# 03_-_WiFi.net
KiCad netlist of a schematic drawn in Altium Designer
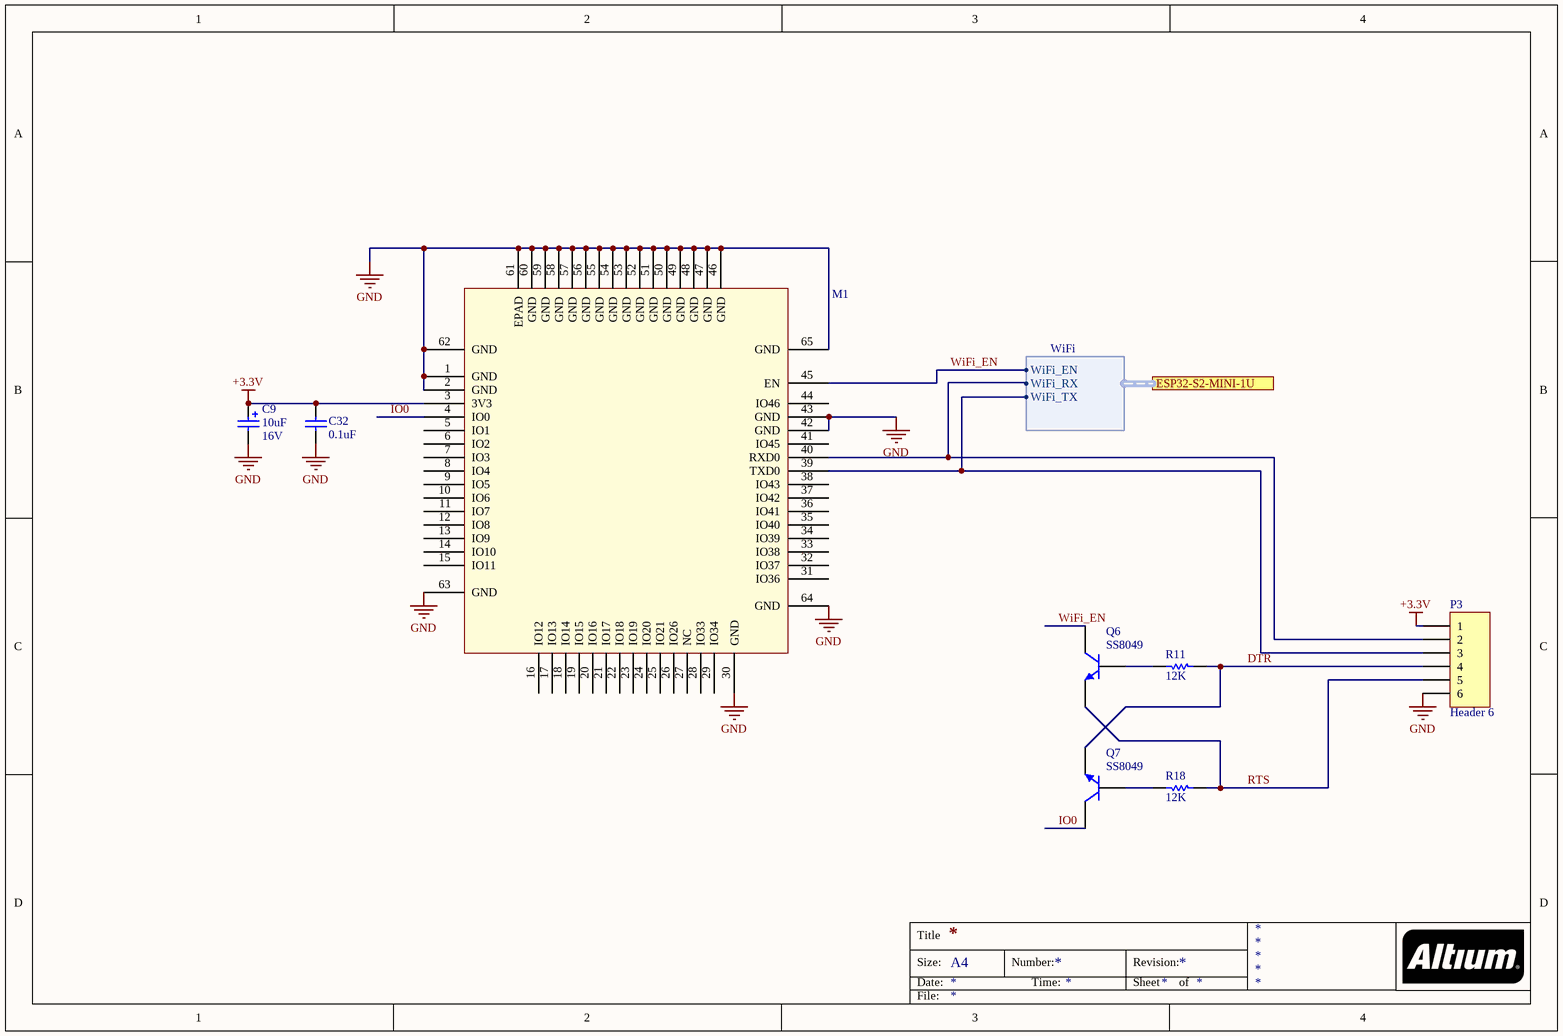
[diagram p0: [03] - WiFi.SchDoc]

(export (version "E")
  (design (tool "Eeschema 10.0.6"))
  (components
    (comp (ref "C9")
      (value "Capacitor Polarized")
      (footprint "Tantalum 3216 A")
      (description "CAP TANT 10UF 10% 16V 1206")
      (fields
        (field (name "MANUFACTURER") "Vishay Sprague")
        (field (name "MANUFACTURER PART NUMBER") "293D106X9016A2TE3")
        (field (name "CAPACITANCE") "10uF")
        (field (name "VOLTAGE RATING") "16V")
      )
      (libsource (lib "Altium_Library") (part "Capacitor Polarized"))
    )
    (comp (ref "C32")
      (value "0.1uF")
      (footprint "0603_C")
      (description "Capacitor")
      (fields (field (name "Comment") "Cap"))
      (libsource (lib "MyLib") (part "Cap"))
    )
    (comp (ref "M1")
      (value "ESP32-S2-MINI-1U _Module")
      (footprint "ESP32-S2-MINI-1U")
      (description "Wi-Fi module")
      (libsource (lib "Blue Tractor-2021") (part "ESP32-S2-MINI-1U _Module"))
    )
    (comp (ref "P3")
      (value "Header 6")
      (footprint "HDR1X6")
      (description "Header, 6-Pin")
      (fields (field (name "PUBLISHER") "Altium Limited"))
      (libsource (lib "Miscellaneous Connectors") (part "Header 6"))
    )
    (comp (ref "Q6")
      (value "SS8049")
      (footprint "SOT23-3")
      (description "NPN Bipolar Transistor")
      (fields (field (name "PUBLISHER") "Altium Limited"))
      (libsource (lib "Miscellaneous Devices") (part "NPN"))
    )
    (comp (ref "Q7")
      (value "SS8049")
      (footprint "SOT23-3")
      (description "NPN Bipolar Transistor")
      (fields (field (name "PUBLISHER") "Altium Limited"))
      (libsource (lib "Miscellaneous Devices") (part "NPN"))
    )
    (comp (ref "R11")
      (value "Res1")
      (footprint "Res-0603")
      (description "Res Thkflm Anti-sulfurated 0603 100K Ohm 5% SMD")
      (fields
        (field (name "MANUFACTURER") "Panasonic")
        (field (name "MANUFACTURER PART NUMBER") "ERJ-U03J104V")
        (field (name "RESISTANCE") "12K")
      )
      (libsource (lib "Altium_Library") (part "Res1"))
    )
    (comp (ref "R18")
      (value "Res1")
      (footprint "Res-0603")
      (description "Res Thkflm Anti-sulfurated 0603 100K Ohm 5% SMD")
      (fields
        (field (name "MANUFACTURER") "Panasonic")
        (field (name "MANUFACTURER PART NUMBER") "ERJ-U03J104V")
        (field (name "RESISTANCE") "12K")
      )
      (libsource (lib "Altium_Library") (part "Res1"))
    )
  )
  (nets
    (net (code "2") (name "+3.3V") (class "Default")
      (node (ref "C32") (pin "2") (pinfunction "2_2") (pintype "passive"))
      (node (ref "C9") (pin "1") (pinfunction "1_1") (pintype "passive"))
      (node (ref "M1") (pin "3") (pinfunction "3V3_3") (pintype "power_in"))
      (node (ref "P3") (pin "1") (pinfunction "1_1") (pintype "passive"))
    )
    (net (code "3") (name "/DTR") (class "Default")
      (node (ref "P3") (pin "4") (pinfunction "4_4") (pintype "passive"))
      (node (ref "Q7") (pin "2") (pinfunction "E_2") (pintype "passive"))
      (node (ref "R11") (pin "2") (pinfunction "2_2") (pintype "passive"))
    )
    (net (code "4") (name "/IO0") (class "Default")
      (node (ref "M1") (pin "4") (pinfunction "IO0_4") (pintype "passive"))
      (node (ref "Q7") (pin "3") (pinfunction "C_3") (pintype "passive"))
    )
    (net (code "5") (name "/RTS") (class "Default")
      (node (ref "P3") (pin "5") (pinfunction "5_5") (pintype "passive"))
      (node (ref "Q6") (pin "2") (pinfunction "E_2") (pintype "passive"))
      (node (ref "R18") (pin "2") (pinfunction "2_2") (pintype "passive"))
    )
    (net (code "6") (name "/WiFi_EN") (class "Default")
      (node (ref "M1") (pin "45") (pinfunction "EN_45") (pintype "power_in"))
      (node (ref "Q6") (pin "3") (pinfunction "C_3") (pintype "passive"))
    )
    (net (code "8") (name "GND") (class "Default")
      (node (ref "C32") (pin "1") (pinfunction "1_1") (pintype "passive"))
      (node (ref "C9") (pin "2") (pinfunction "2_2") (pintype "passive"))
      (node (ref "M1") (pin "1") (pinfunction "GND_1") (pintype "power_in"))
      (node (ref "M1") (pin "2") (pinfunction "GND_2") (pintype "power_in"))
      (node (ref "M1") (pin "30") (pinfunction "GND_30") (pintype "power_in"))
      (node (ref "M1") (pin "42") (pinfunction "GND_42") (pintype "passive"))
      (node (ref "M1") (pin "43") (pinfunction "GND_43") (pintype "passive"))
      (node (ref "M1") (pin "46") (pinfunction "GND_46") (pintype "power_in"))
      (node (ref "M1") (pin "47") (pinfunction "GND_47") (pintype "power_in"))
      (node (ref "M1") (pin "48") (pinfunction "GND_48") (pintype "power_in"))
      (node (ref "M1") (pin "49") (pinfunction "GND_49") (pintype "power_in"))
      (node (ref "M1") (pin "50") (pinfunction "GND_50") (pintype "power_in"))
      (node (ref "M1") (pin "51") (pinfunction "GND_51") (pintype "power_in"))
      (node (ref "M1") (pin "52") (pinfunction "GND_52") (pintype "power_in"))
      (node (ref "M1") (pin "53") (pinfunction "GND_53") (pintype "power_in"))
      (node (ref "M1") (pin "54") (pinfunction "GND_54") (pintype "power_in"))
      (node (ref "M1") (pin "55") (pinfunction "GND_55") (pintype "power_in"))
      (node (ref "M1") (pin "56") (pinfunction "GND_56") (pintype "power_in"))
      (node (ref "M1") (pin "57") (pinfunction "GND_57") (pintype "power_in"))
      (node (ref "M1") (pin "58") (pinfunction "GND_58") (pintype "power_in"))
      (node (ref "M1") (pin "59") (pinfunction "GND_59") (pintype "power_in"))
      (node (ref "M1") (pin "60") (pinfunction "GND_60") (pintype "power_in"))
      (node (ref "M1") (pin "61") (pinfunction "EPAD_61") (pintype "power_in"))
      (node (ref "M1") (pin "62") (pinfunction "GND_62") (pintype "power_in"))
      (node (ref "M1") (pin "63") (pinfunction "GND_63") (pintype "passive"))
      (node (ref "M1") (pin "64") (pinfunction "GND_64") (pintype "passive"))
      (node (ref "M1") (pin "65") (pinfunction "GND_65") (pintype "power_in"))
      (node (ref "P3") (pin "6") (pinfunction "6_6") (pintype "passive"))
    )
    (net (code "9") (name "Net-(M1-RXD0)") (class "Default")
      (node (ref "M1") (pin "40") (pinfunction "RXD0_40") (pintype "passive"))
      (node (ref "P3") (pin "2") (pinfunction "2_2") (pintype "passive"))
    )
    (net (code "10") (name "Net-(M1-TXD0)") (class "Default")
      (node (ref "M1") (pin "39") (pinfunction "TXD0_39") (pintype "passive"))
      (node (ref "P3") (pin "3") (pinfunction "3_3") (pintype "passive"))
    )
    (net (code "11") (name "Net-(Q6-B)") (class "Default")
      (node (ref "Q6") (pin "1") (pinfunction "B_1") (pintype "passive"))
      (node (ref "R11") (pin "1") (pinfunction "1_1") (pintype "passive"))
    )
    (net (code "12") (name "Net-(Q7-B)") (class "Default")
      (node (ref "Q7") (pin "1") (pinfunction "B_1") (pintype "passive"))
      (node (ref "R18") (pin "1") (pinfunction "1_1") (pintype "passive"))
    )
    (net (code "13") (name "unconnected-(M1-IO1-Pad5)") (class "Default")
      (node (ref "M1") (pin "5") (pinfunction "IO1_5") (pintype "passive"))
    )
    (net (code "14") (name "unconnected-(M1-IO2-Pad6)") (class "Default")
      (node (ref "M1") (pin "6") (pinfunction "IO2_6") (pintype "passive"))
    )
    (net (code "15") (name "unconnected-(M1-IO3-Pad7)") (class "Default")
      (node (ref "M1") (pin "7") (pinfunction "IO3_7") (pintype "passive"))
    )
    (net (code "16") (name "unconnected-(M1-IO4-Pad8)") (class "Default")
      (node (ref "M1") (pin "8") (pinfunction "IO4_8") (pintype "passive"))
    )
    (net (code "17") (name "unconnected-(M1-IO5-Pad9)") (class "Default")
      (node (ref "M1") (pin "9") (pinfunction "IO5_9") (pintype "passive"))
    )
    (net (code "18") (name "unconnected-(M1-IO6-Pad10)") (class "Default")
      (node (ref "M1") (pin "10") (pinfunction "IO6_10") (pintype "passive"))
    )
    (net (code "19") (name "unconnected-(M1-IO7-Pad11)") (class "Default")
      (node (ref "M1") (pin "11") (pinfunction "IO7_11") (pintype "passive"))
    )
    (net (code "20") (name "unconnected-(M1-IO8-Pad12)") (class "Default")
      (node (ref "M1") (pin "12") (pinfunction "IO8_12") (pintype "passive"))
    )
    (net (code "21") (name "unconnected-(M1-IO9-Pad13)") (class "Default")
      (node (ref "M1") (pin "13") (pinfunction "IO9_13") (pintype "passive"))
    )
    (net (code "22") (name "unconnected-(M1-IO10-Pad14)") (class "Default")
      (node (ref "M1") (pin "14") (pinfunction "IO10_14") (pintype "passive"))
    )
    (net (code "23") (name "unconnected-(M1-IO11-Pad15)") (class "Default")
      (node (ref "M1") (pin "15") (pinfunction "IO11_15") (pintype "passive"))
    )
    (net (code "24") (name "unconnected-(M1-IO12-Pad16)") (class "Default")
      (node (ref "M1") (pin "16") (pinfunction "IO12_16") (pintype "passive"))
    )
    (net (code "25") (name "unconnected-(M1-IO13-Pad17)") (class "Default")
      (node (ref "M1") (pin "17") (pinfunction "IO13_17") (pintype "passive"))
    )
    (net (code "26") (name "unconnected-(M1-IO14-Pad18)") (class "Default")
      (node (ref "M1") (pin "18") (pinfunction "IO14_18") (pintype "passive"))
    )
    (net (code "27") (name "unconnected-(M1-IO15-Pad19)") (class "Default")
      (node (ref "M1") (pin "19") (pinfunction "IO15_19") (pintype "passive"))
    )
    (net (code "28") (name "unconnected-(M1-IO16-Pad20)") (class "Default")
      (node (ref "M1") (pin "20") (pinfunction "IO16_20") (pintype "passive"))
    )
    (net (code "29") (name "unconnected-(M1-IO17-Pad21)") (class "Default")
      (node (ref "M1") (pin "21") (pinfunction "IO17_21") (pintype "passive"))
    )
    (net (code "30") (name "unconnected-(M1-IO18-Pad22)") (class "Default")
      (node (ref "M1") (pin "22") (pinfunction "IO18_22") (pintype "passive"))
    )
    (net (code "31") (name "unconnected-(M1-IO19-Pad23)") (class "Default")
      (node (ref "M1") (pin "23") (pinfunction "IO19_23") (pintype "passive"))
    )
    (net (code "32") (name "unconnected-(M1-IO20-Pad24)") (class "Default")
      (node (ref "M1") (pin "24") (pinfunction "IO20_24") (pintype "passive"))
    )
    (net (code "33") (name "unconnected-(M1-IO21-Pad25)") (class "Default")
      (node (ref "M1") (pin "25") (pinfunction "IO21_25") (pintype "passive"))
    )
    (net (code "34") (name "unconnected-(M1-IO26-Pad26)") (class "Default")
      (node (ref "M1") (pin "26") (pinfunction "IO26_26") (pintype "passive"))
    )
    (net (code "35") (name "unconnected-(M1-IO33-Pad28)") (class "Default")
      (node (ref "M1") (pin "28") (pinfunction "IO33_28") (pintype "passive"))
    )
    (net (code "36") (name "unconnected-(M1-IO34-Pad29)") (class "Default")
      (node (ref "M1") (pin "29") (pinfunction "IO34_29") (pintype "passive"))
    )
    (net (code "37") (name "unconnected-(M1-IO36-Pad31)") (class "Default")
      (node (ref "M1") (pin "31") (pinfunction "IO36_31") (pintype "passive"))
    )
    (net (code "38") (name "unconnected-(M1-IO37-Pad32)") (class "Default")
      (node (ref "M1") (pin "32") (pinfunction "IO37_32") (pintype "passive"))
    )
    (net (code "39") (name "unconnected-(M1-IO38-Pad33)") (class "Default")
      (node (ref "M1") (pin "33") (pinfunction "IO38_33") (pintype "passive"))
    )
    (net (code "40") (name "unconnected-(M1-IO39-Pad34)") (class "Default")
      (node (ref "M1") (pin "34") (pinfunction "IO39_34") (pintype "passive"))
    )
    (net (code "41") (name "unconnected-(M1-IO40-Pad35)") (class "Default")
      (node (ref "M1") (pin "35") (pinfunction "IO40_35") (pintype "passive"))
    )
    (net (code "42") (name "unconnected-(M1-IO41-Pad36)") (class "Default")
      (node (ref "M1") (pin "36") (pinfunction "IO41_36") (pintype "passive"))
    )
    (net (code "43") (name "unconnected-(M1-IO42-Pad37)") (class "Default")
      (node (ref "M1") (pin "37") (pinfunction "IO42_37") (pintype "passive"))
    )
    (net (code "44") (name "unconnected-(M1-IO43-Pad38)") (class "Default")
      (node (ref "M1") (pin "38") (pinfunction "IO43_38") (pintype "passive"))
    )
    (net (code "45") (name "unconnected-(M1-IO45-Pad41)") (class "Default")
      (node (ref "M1") (pin "41") (pinfunction "IO45_41") (pintype "passive"))
    )
    (net (code "46") (name "unconnected-(M1-IO46-Pad44)") (class "Default")
      (node (ref "M1") (pin "44") (pinfunction "IO46_44") (pintype "passive"))
    )
    (net (code "47") (name "unconnected-(M1-NC-Pad27)") (class "Default")
      (node (ref "M1") (pin "27") (pinfunction "NC_27") (pintype "passive"))
    )
  )
)
